# DAC8552.net
KiCad netlist of a schematic drawn in Altium Designer
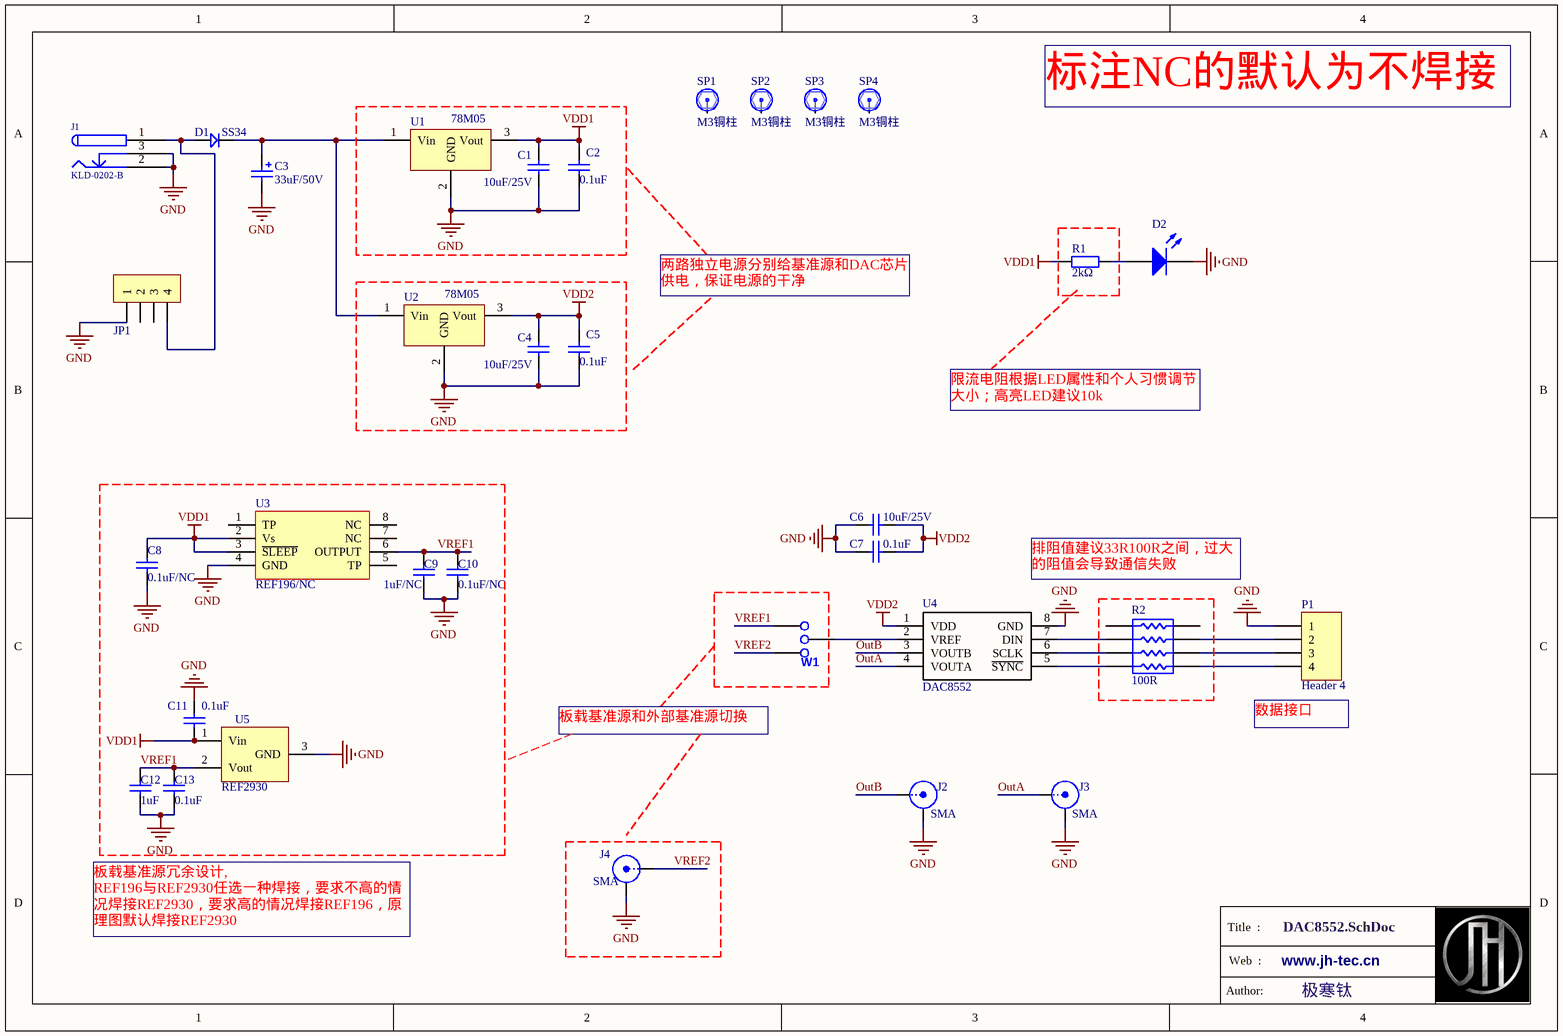
[diagram p0: DAC8552.SchDoc]

(export (version "E")
  (design (tool "Eeschema 10.0.6"))
  (components
    (comp (ref "C1")
      (value "10uF/25V/0603")
      (footprint "CAP MLCC 0805")
      (description "Capacitor (Semiconductor SIM Model)")
      (fields (field (name "SCH NAME") "10uF/25V"))
      (libsource (lib "mylib") (part "Cap Semi"))
    )
    (comp (ref "C2")
      (value "0.1uF")
      (footprint "JH_PCB:C0603")
      (description "Capacitor (Semiconductor SIM Model)")
      (fields (field (name "PUBLISHER") "Altium Limited"))
      (libsource (lib "mylib") (part "Cap Semi"))
    )
    (comp (ref "C3")
      (value "33uF/50V")
      (footprint "JH_PCB:C6.3*7.7")
      (description "Polarized Capacitor (Surface Mount)")
      (fields (field (name "PUBLISHER") "Altium Limited"))
      (libsource (lib "mylib") (part "Cap Pol3_1"))
    )
    (comp (ref "C4")
      (value "10uF/25V/0603")
      (footprint "CAP MLCC 0805")
      (description "Capacitor (Semiconductor SIM Model)")
      (fields (field (name "SCH NAME") "10uF/25V"))
      (libsource (lib "mylib") (part "Cap Semi"))
    )
    (comp (ref "C5")
      (value "0.1uF")
      (footprint "JH_PCB:C0603")
      (description "Capacitor (Semiconductor SIM Model)")
      (fields (field (name "PUBLISHER") "Altium Limited"))
      (libsource (lib "mylib") (part "Cap Semi"))
    )
    (comp (ref "C6")
      (value "10uF/25V/0603")
      (footprint "CAP MLCC 0805")
      (description "Capacitor (Semiconductor SIM Model)")
      (fields (field (name "SCH NAME") "10uF/25V"))
      (libsource (lib "mylib") (part "Cap Semi"))
    )
    (comp (ref "C7")
      (value "0.1uF")
      (footprint "JH_PCB:C0603")
      (description "Capacitor (Semiconductor SIM Model)")
      (fields (field (name "PUBLISHER") "Altium Limited"))
      (libsource (lib "mylib") (part "Cap Semi"))
    )
    (comp (ref "C8")
      (value "0.1uF/NC")
      (footprint "JH_PCB:C0603")
      (description "Capacitor (Semiconductor SIM Model)")
      (fields (field (name "PUBLISHER") "Altium Limited"))
      (libsource (lib "mylib") (part "Cap Semi"))
    )
    (comp (ref "C9")
      (value "1uF/NC")
      (footprint "JH_PCB:C0603")
      (description "Capacitor (Semiconductor SIM Model)")
      (fields (field (name "PUBLISHER") "Altium Limited"))
      (libsource (lib "mylib") (part "Cap Semi"))
    )
    (comp (ref "C10")
      (value "0.1uF/NC")
      (footprint "JH_PCB:C0603")
      (description "Capacitor (Semiconductor SIM Model)")
      (fields (field (name "PUBLISHER") "Altium Limited"))
      (libsource (lib "mylib") (part "Cap Semi"))
    )
    (comp (ref "C11")
      (value "0.1uF")
      (footprint "JH_PCB:C0603")
      (description "Capacitor")
      (fields (field (name "PUBLISHER") "Altium Limited"))
      (libsource (lib "Miscellaneous Devices") (part "Cap"))
    )
    (comp (ref "C12")
      (value "1uF")
      (footprint "JH_PCB:C0603")
      (description "Capacitor (Semiconductor SIM Model)")
      (fields (field (name "PUBLISHER") "Altium Limited"))
      (libsource (lib "mylib") (part "Cap Semi"))
    )
    (comp (ref "C13")
      (value "0.1uF")
      (footprint "JH_PCB:C0603")
      (description "Capacitor (Semiconductor SIM Model)")
      (fields (field (name "PUBLISHER") "Altium Limited"))
      (libsource (lib "mylib") (part "Cap Semi"))
    )
    (comp (ref "D1")
      (value "SS34")
      (footprint "JH_PCB:DO-214AC")
      (description "1N4148")
      (libsource (lib "ATK-SIM900A") (part "D"))
    )
    (comp (ref "D2")
      (value "LED3")
      (footprint "JH_PCB:LED_GREEN_0603")
      (description "Typical BLUE SiC LED")
      (fields (field (name "PUBLISHER") "Altium Limited"))
      (libsource (lib "mylib") (part "LED3"))
    )
    (comp (ref "J1")
      (value "KLD-0202-B")
      (footprint "JH_PCB:DC005")
      (description "Low Voltage Power Supply Connector")
      (fields (field (name "MANUFACTURER") "Kycon"))
      (libsource (lib "My3D") (part "KLD-0202-B"))
    )
    (comp (ref "J2") (value "SMA") (footprint "JH_PCB:SMA_3D") (libsource (lib "常用sch") (part "SMA")))
    (comp (ref "J3") (value "SMA") (footprint "JH_PCB:SMA_3D") (libsource (lib "常用sch") (part "SMA")))
    (comp (ref "J4") (value "SMA") (footprint "JH_PCB:SMA_RJ45") (libsource (lib "常用sch") (part "SMA")))
    (comp (ref "JP1")
      (value "HDR-1X4")
      (footprint "XH2.54-WI-4P")
      (description "4P接插件")
      (libsource (lib "XH2.54") (part "Header 4"))
    )
    (comp (ref "P1")
      (value "Header 4")
      (footprint "JH_PCB:XH2.54x4")
      (description "Header, 4-Pin")
      (fields (field (name "PUBLISHER") "*"))
      (libsource (lib "常用sch") (part "Header 4"))
    )
    (comp (ref "R1")
      (value "2kΩ")
      (footprint "JH_PCB:R0603")
      (description "Resistor")
      (fields (field (name "PUBLISHER") "Altium Limited"))
      (libsource (lib "Miscellaneous Devices") (part "Res2"))
    )
    (comp (ref "R2") (value "100R") (footprint "JH_PCB:RA4") (libsource (lib "AD9854") (part "RESPACK1")))
    (comp (ref "SP1")
      (value "M3铜柱")
      (footprint "M3x4+6_L")
      (description "铜柱")
      (libsource (lib "铜柱-测试点-电池座-蜂鸣器") (part "铜柱加头小焊盘"))
    )
    (comp (ref "SP2")
      (value "M3铜柱")
      (footprint "M3x4+6_L")
      (description "铜柱")
      (libsource (lib "铜柱-测试点-电池座-蜂鸣器") (part "铜柱加头小焊盘"))
    )
    (comp (ref "SP3")
      (value "M3铜柱")
      (footprint "M3x4+6_L")
      (description "铜柱")
      (libsource (lib "铜柱-测试点-电池座-蜂鸣器") (part "铜柱加头小焊盘"))
    )
    (comp (ref "SP4")
      (value "M3铜柱")
      (footprint "M3x4+6_L")
      (description "铜柱")
      (libsource (lib "铜柱-测试点-电池座-蜂鸣器") (part "铜柱加头小焊盘"))
    )
    (comp (ref "U1")
      (value "78M05")
      (footprint "SOT223_M")
      (libsource (lib "altium-import") (part "root_0_78L05_"))
    )
    (comp (ref "U2")
      (value "78M05")
      (footprint "SOT223_M")
      (libsource (lib "altium-import") (part "root_0_78L05_"))
    )
    (comp (ref "U3")
      (value "REF196/NC")
      (footprint "JH_PCB:SOP-8")
      (libsource (lib "altium-import") (part "root_0_REF19x_"))
    )
    (comp (ref "U4")
      (value "DAC8552")
      (footprint "IC:SOP65P490X110-8N")
      (description "Integrated Circuit")
      (fields (field (name "MANUFACTURER_PART_NUMBER") "DAC8552IDGKT"))
      (libsource (lib "ADI") (part "DAC8552IDGKT"))
    )
    (comp (ref "U5")
      (value "REF2930")
      (footprint "MY_IC:SOT23-3")
      (libsource (lib "altium-import") (part "root_0_REF29XX_"))
    )
    (comp (ref "W1")
      (value "key")
      (footprint "JH_PCB:HDR1X3")
      (description "KEY 1 to 2")
      (libsource (lib "*") (part "W"))
    )
  )
  (nets
    (net (code "1") (name "/OutA") (class "Default")
      (node (ref "J3") (pin "1") (pinfunction "X_1") (pintype "passive"))
      (node (ref "U4") (pin "4") (pinfunction "VOUTA_4") (pintype "passive"))
    )
    (net (code "2") (name "/OutB") (class "Default")
      (node (ref "J2") (pin "1") (pinfunction "X_1") (pintype "passive"))
      (node (ref "U4") (pin "3") (pinfunction "VOUTB_3") (pintype "passive"))
    )
    (net (code "3") (name "/VREF1") (class "Default")
      (node (ref "C10") (pin "1") (pinfunction "1_1") (pintype "passive"))
      (node (ref "C12") (pin "1") (pinfunction "1_1") (pintype "passive"))
      (node (ref "C13") (pin "1") (pinfunction "1_1") (pintype "passive"))
      (node (ref "C9") (pin "1") (pinfunction "1_1") (pintype "passive"))
      (node (ref "U3") (pin "6") (pinfunction "OUTPUT_6") (pintype "passive"))
      (node (ref "U5") (pin "2") (pinfunction "Vout_2") (pintype "passive"))
      (node (ref "W1") (pin "3") (pinfunction "3_3") (pintype "power_in"))
    )
    (net (code "4") (name "/VREF2") (class "Default")
      (node (ref "J4") (pin "1") (pinfunction "X_1") (pintype "passive"))
      (node (ref "W1") (pin "1") (pinfunction "1_1") (pintype "power_in"))
    )
    (net (code "5") (name "GND") (class "Default")
      (node (ref "C1") (pin "2") (pinfunction "2_2") (pintype "passive"))
      (node (ref "C10") (pin "2") (pinfunction "2_2") (pintype "passive"))
      (node (ref "C11") (pin "2") (pinfunction "2_2") (pintype "passive"))
      (node (ref "C12") (pin "2") (pinfunction "2_2") (pintype "passive"))
      (node (ref "C13") (pin "2") (pinfunction "2_2") (pintype "passive"))
      (node (ref "C2") (pin "2") (pinfunction "2_2") (pintype "passive"))
      (node (ref "C3") (pin "2") (pinfunction "2_2") (pintype "passive"))
      (node (ref "C4") (pin "2") (pinfunction "2_2") (pintype "passive"))
      (node (ref "C5") (pin "2") (pinfunction "2_2") (pintype "passive"))
      (node (ref "C6") (pin "1") (pinfunction "1_1") (pintype "passive"))
      (node (ref "C7") (pin "2") (pinfunction "2_2") (pintype "passive"))
      (node (ref "C8") (pin "2") (pinfunction "2_2") (pintype "passive"))
      (node (ref "C9") (pin "2") (pinfunction "2_2") (pintype "passive"))
      (node (ref "D2") (pin "2") (pinfunction "K_2") (pintype "passive"))
      (node (ref "J1") (pin "2") (pintype "power_in"))
      (node (ref "J1") (pin "3") (pintype "power_in"))
      (node (ref "J2") (pin "2") (pinfunction "Y_2") (pintype "passive"))
      (node (ref "J3") (pin "2") (pinfunction "Y_2") (pintype "passive"))
      (node (ref "J4") (pin "2") (pinfunction "Y_2") (pintype "passive"))
      (node (ref "JP1") (pin "1") (pinfunction "1_1") (pintype "passive"))
      (node (ref "P1") (pin "1") (pinfunction "1_1") (pintype "passive"))
      (node (ref "U1") (pin "2") (pinfunction "GND_2") (pintype "passive"))
      (node (ref "U2") (pin "2") (pinfunction "GND_2") (pintype "passive"))
      (node (ref "U3") (pin "4") (pinfunction "GND_4") (pintype "passive"))
      (node (ref "U4") (pin "8") (pinfunction "GND_8") (pintype "passive"))
      (node (ref "U5") (pin "3") (pinfunction "GND_3") (pintype "passive"))
    )
    (net (code "6") (name "Net-(D1-Pad1)") (class "Default")
      (node (ref "D1") (pin "1") (pintype "passive"))
      (node (ref "J1") (pin "1") (pintype "power_in"))
      (node (ref "JP1") (pin "4") (pinfunction "4_4") (pintype "passive"))
    )
    (net (code "7") (name "Net-(D2-A)") (class "Default")
      (node (ref "D2") (pin "1") (pinfunction "A_1") (pintype "passive"))
      (node (ref "R1") (pin "1") (pinfunction "1_1") (pintype "passive"))
    )
    (net (code "8") (name "Net-(P1-Pad2)") (class "Default")
      (node (ref "P1") (pin "2") (pinfunction "2_2") (pintype "passive"))
      (node (ref "R2") (pin "4") (pinfunction "4_4") (pintype "passive"))
    )
    (net (code "9") (name "Net-(P1-Pad3)") (class "Default")
      (node (ref "P1") (pin "3") (pinfunction "3_3") (pintype "passive"))
      (node (ref "R2") (pin "6") (pinfunction "6_6") (pintype "passive"))
    )
    (net (code "10") (name "Net-(P1-Pad4)") (class "Default")
      (node (ref "P1") (pin "4") (pinfunction "4_4") (pintype "passive"))
      (node (ref "R2") (pin "8") (pinfunction "8_8") (pintype "passive"))
    )
    (net (code "11") (name "Net-(U1-Vin)") (class "Default")
      (node (ref "C3") (pin "1") (pinfunction "1_1") (pintype "passive"))
      (node (ref "D1") (pin "2") (pintype "passive"))
      (node (ref "U1") (pin "1") (pinfunction "Vin_1") (pintype "passive"))
      (node (ref "U2") (pin "1") (pinfunction "Vin_1") (pintype "passive"))
    )
    (net (code "12") (name "Net-(U4-DIN)") (class "Default")
      (node (ref "R2") (pin "3") (pinfunction "3_3") (pintype "passive"))
      (node (ref "U4") (pin "7") (pinfunction "DIN_7") (pintype "passive"))
    )
    (net (code "13") (name "Net-(U4-SCLK)") (class "Default")
      (node (ref "R2") (pin "5") (pinfunction "5_5") (pintype "passive"))
      (node (ref "U4") (pin "6") (pinfunction "SCLK_6") (pintype "passive"))
    )
    (net (code "14") (name "Net-(U4-VREF)") (class "Default")
      (node (ref "U4") (pin "2") (pinfunction "VREF_2") (pintype "passive"))
      (node (ref "W1") (pin "2") (pinfunction "2_2") (pintype "power_in"))
    )
    (net (code "15") (name "Net-(U4-~{SYNC})") (class "Default")
      (node (ref "R2") (pin "7") (pinfunction "7_7") (pintype "passive"))
      (node (ref "U4") (pin "5") (pinfunction "~{SYNC}_5") (pintype "passive"))
    )
    (net (code "16") (name "VDD1") (class "Default")
      (node (ref "C1") (pin "1") (pinfunction "1_1") (pintype "passive"))
      (node (ref "C11") (pin "1") (pinfunction "1_1") (pintype "passive"))
      (node (ref "C2") (pin "1") (pinfunction "1_1") (pintype "passive"))
      (node (ref "C8") (pin "1") (pinfunction "1_1") (pintype "passive"))
      (node (ref "R1") (pin "2") (pinfunction "2_2") (pintype "passive"))
      (node (ref "U1") (pin "3") (pinfunction "Vout_3") (pintype "passive"))
      (node (ref "U3") (pin "2") (pinfunction "Vs_2") (pintype "passive"))
      (node (ref "U3") (pin "3") (pinfunction "~{SLEEP}_3") (pintype "passive"))
      (node (ref "U5") (pin "1") (pinfunction "Vin_1") (pintype "passive"))
    )
    (net (code "17") (name "VDD2") (class "Default")
      (node (ref "C4") (pin "1") (pinfunction "1_1") (pintype "passive"))
      (node (ref "C5") (pin "1") (pinfunction "1_1") (pintype "passive"))
      (node (ref "C6") (pin "2") (pinfunction "2_2") (pintype "passive"))
      (node (ref "C7") (pin "1") (pinfunction "1_1") (pintype "passive"))
      (node (ref "U2") (pin "3") (pinfunction "Vout_3") (pintype "passive"))
      (node (ref "U4") (pin "1") (pinfunction "VDD_1") (pintype "passive"))
    )
    (net (code "18") (name "unconnected-(JP1-Pad2)") (class "Default")
      (node (ref "JP1") (pin "2") (pinfunction "2_2") (pintype "passive"))
    )
    (net (code "19") (name "unconnected-(JP1-Pad3)") (class "Default")
      (node (ref "JP1") (pin "3") (pinfunction "3_3") (pintype "passive"))
    )
    (net (code "20") (name "unconnected-(R2-Pad1)") (class "Default")
      (node (ref "R2") (pin "1") (pinfunction "1_1") (pintype "passive"))
    )
    (net (code "21") (name "unconnected-(R2-Pad2)") (class "Default")
      (node (ref "R2") (pin "2") (pinfunction "2_2") (pintype "passive"))
    )
    (net (code "22") (name "unconnected-(SP1-Pad1)") (class "Default")
      (node (ref "SP1") (pin "1") (pinfunction "1_1") (pintype "passive"))
    )
    (net (code "23") (name "unconnected-(SP2-Pad1)") (class "Default")
      (node (ref "SP2") (pin "1") (pinfunction "1_1") (pintype "passive"))
    )
    (net (code "24") (name "unconnected-(SP3-Pad1)") (class "Default")
      (node (ref "SP3") (pin "1") (pinfunction "1_1") (pintype "passive"))
    )
    (net (code "25") (name "unconnected-(SP4-Pad1)") (class "Default")
      (node (ref "SP4") (pin "1") (pinfunction "1_1") (pintype "passive"))
    )
    (net (code "26") (name "unconnected-(U3-NC-Pad7)") (class "Default")
      (node (ref "U3") (pin "7") (pinfunction "NC_7") (pintype "passive"))
    )
    (net (code "27") (name "unconnected-(U3-NC-Pad8)") (class "Default")
      (node (ref "U3") (pin "8") (pinfunction "NC_8") (pintype "passive"))
    )
    (net (code "28") (name "unconnected-(U3-TP-Pad1)") (class "Default")
      (node (ref "U3") (pin "1") (pinfunction "TP_1") (pintype "passive"))
    )
    (net (code "29") (name "unconnected-(U3-TP-Pad5)") (class "Default")
      (node (ref "U3") (pin "5") (pinfunction "TP_5") (pintype "passive"))
    )
  )
)
